# top_power.net
KiCad netlist of a schematic drawn in Altium Designer
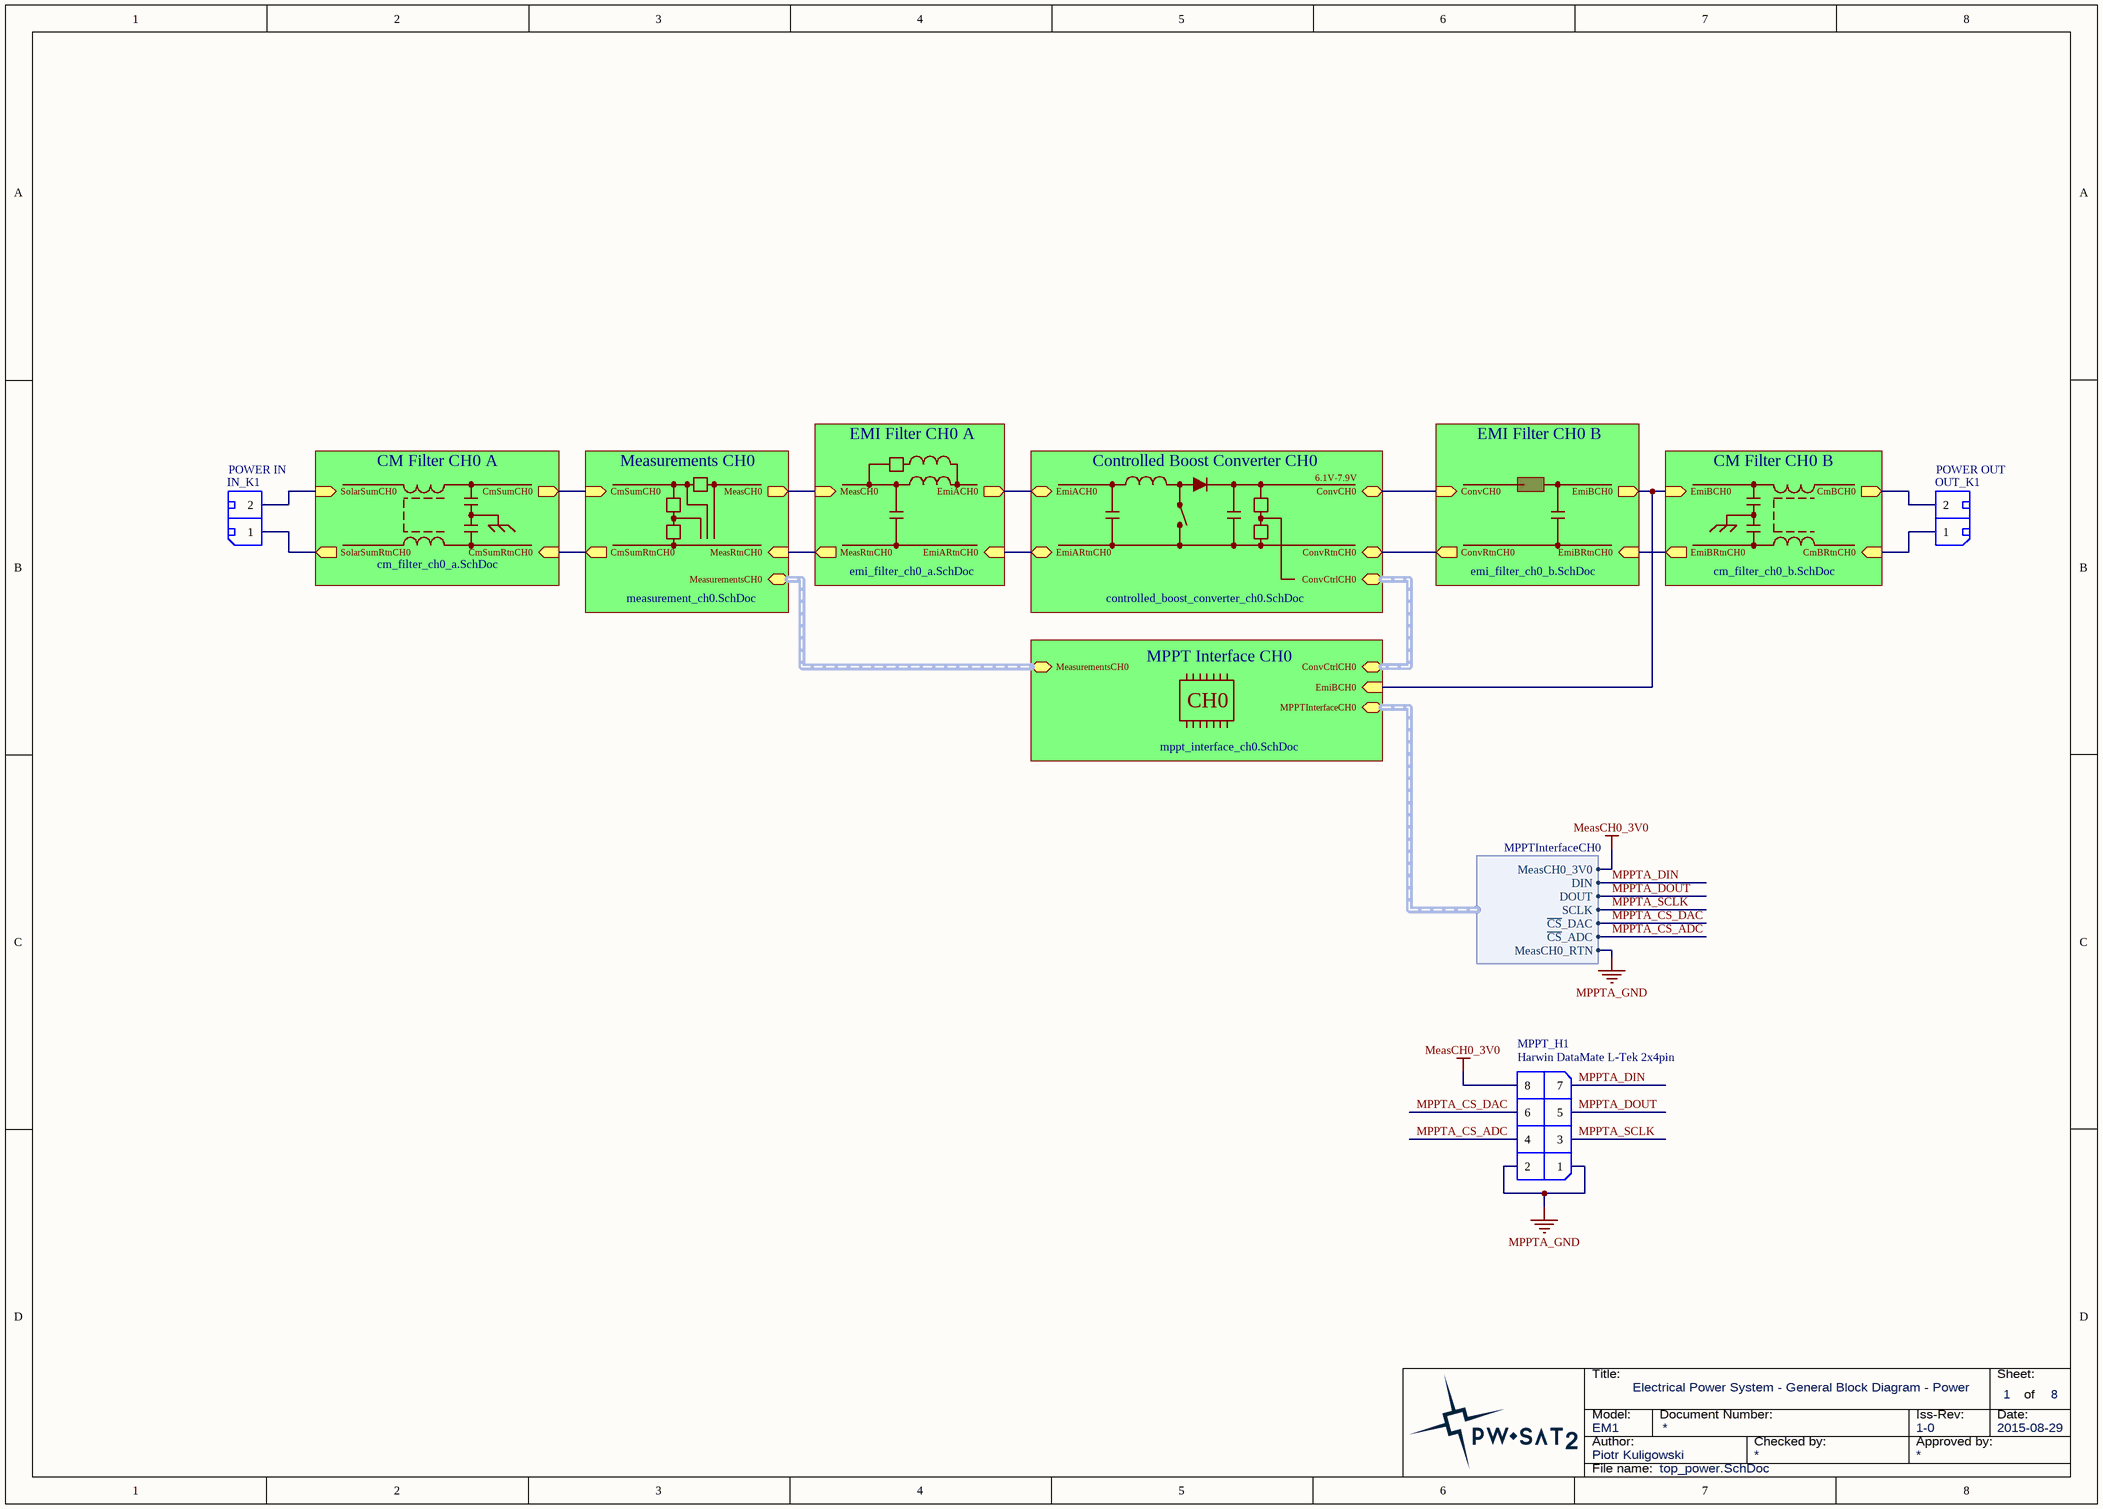
[diagram p0: top_power.SchDoc]

(export (version "E")
  (design (tool "Eeschema 10.0.6"))
  (components
    (comp (ref "IN_K1")
      (value "TB-2.5-PD-xx")
      (footprint "TerminalBlock_Spring_2.54_2-R")
      (description "Terminal block with spring, 2-pin, 2.54mm pitch, right angle.")
      (fields (field (name "PROVIDERPARTNUMBER") "POWER IN") (field (name "PROVIDER") "TME.eu"))
      (libsource (lib "connectors_printed-circuit-board") (part "TerminalBlock_Spring_2.54_2-R"))
    )
    (comp (ref "MPPT_H1")
      (value "Harwin DataMate L-Tek 2x4pin")
      (footprint "Harwin_Datamate_L-Tek_M80-8670805")
      (description "Harwin DataMate L-Tek, 2mm pitch, 2x4pin.")
      (libsource (lib "connectors_printed-circuit-board") (part "Harwin_Datamate_L-Tek_2x4pin"))
    )
    (comp (ref "OUT_K1")
      (value "TB-2.5-PD-xx")
      (footprint "TerminalBlock_Spring_2.54_2-R")
      (description "Terminal block with spring, 2-pin, 2.54mm pitch, right angle.")
      (fields (field (name "PROVIDERPARTNUMBER") "POWER OUT") (field (name "PROVIDER") "TME.eu"))
      (libsource (lib "connectors_printed-circuit-board") (part "TerminalBlock_Spring_2.54_2-R"))
    )
  )
  (nets
    (net (code "2") (name "/CmBCH0") (class "Default")
      (node (ref "OUT_K1") (pin "2") (pinfunction "2_2") (pintype "passive"))
    )
    (net (code "3") (name "/CmBRtnCH0") (class "Default")
      (node (ref "OUT_K1") (pin "1") (pinfunction "1_1") (pintype "passive"))
    )
    (net (code "13") (name "/MPPTA_CS_ADC") (class "Default")
      (node (ref "MPPT_H1") (pin "4") (pinfunction "4_4") (pintype "passive"))
    )
    (net (code "14") (name "/MPPTA_CS_DAC") (class "Default")
      (node (ref "MPPT_H1") (pin "6") (pinfunction "6_6") (pintype "passive"))
    )
    (net (code "15") (name "/MPPTA_DIN") (class "Default")
      (node (ref "MPPT_H1") (pin "7") (pinfunction "7_7") (pintype "passive"))
    )
    (net (code "16") (name "/MPPTA_DOUT") (class "Default")
      (node (ref "MPPT_H1") (pin "5") (pinfunction "5_5") (pintype "passive"))
    )
    (net (code "17") (name "/MPPTA_SCLK") (class "Default")
      (node (ref "MPPT_H1") (pin "3") (pinfunction "3_3") (pintype "passive"))
    )
    (net (code "21") (name "/SolarSumCH0") (class "Default")
      (node (ref "IN_K1") (pin "2") (pinfunction "2_2") (pintype "passive"))
    )
    (net (code "22") (name "/SolarSumRtnCH0") (class "Default")
      (node (ref "IN_K1") (pin "1") (pinfunction "1_1") (pintype "passive"))
    )
    (net (code "24") (name "MPPTA_GND") (class "Default")
      (node (ref "MPPT_H1") (pin "1") (pinfunction "1_1") (pintype "passive"))
      (node (ref "MPPT_H1") (pin "2") (pinfunction "2_2") (pintype "passive"))
    )
    (net (code "25") (name "MeasCH0_3V0") (class "Default")
      (node (ref "MPPT_H1") (pin "8") (pinfunction "8_8") (pintype "passive"))
    )
  )
)
